# GPS.net
KiCad netlist of a schematic drawn in Altium Designer
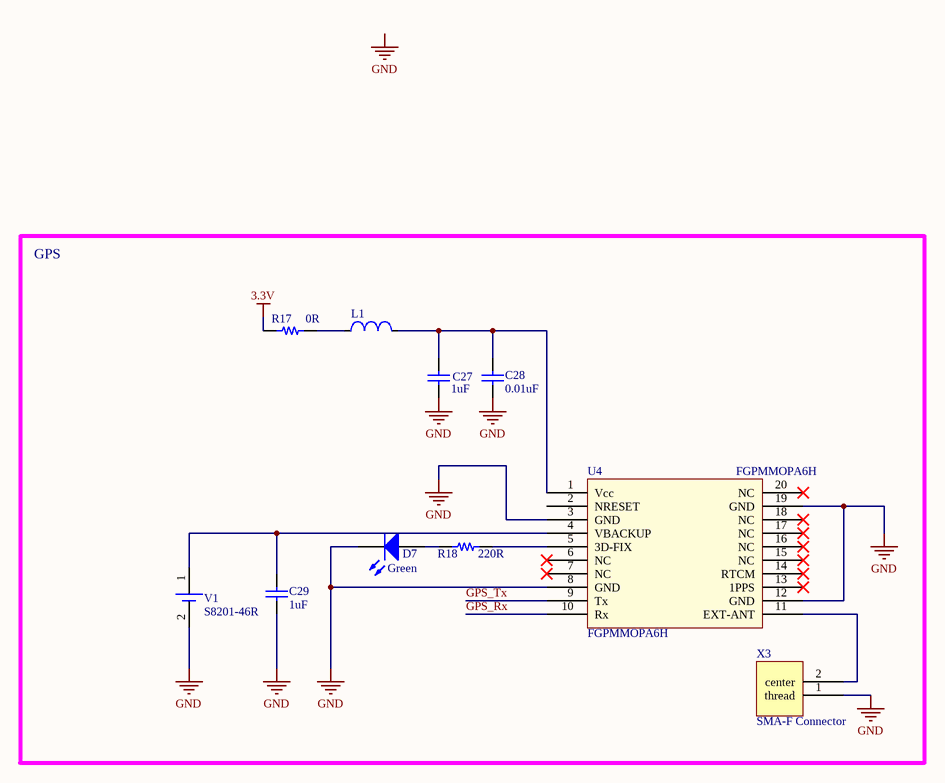
[diagram p0: GPS.SchDoc]

(export (version "E")
  (design (tool "Eeschema 10.0.6"))
  (components
    (comp (ref "C27")
      (value "1uF")
      (footprint "Capacitors:C0603")
      (description "1uF ceramic capacitor")
      (fields (field (name "MANUFACTURER") "TDK Corporation") (field (name "TOLERANCE") "20%"))
      (libsource (lib "Capacitors") (part "CAP CER 0603 1uF 25V X7R 20%"))
    )
    (comp (ref "C28")
      (value "0.01uF")
      (footprint "Capacitors:C0603")
      (description "0.01uF ceramic capacitor")
      (fields (field (name "MANUFACTURER") "TDK Corporation") (field (name "TOLERANCE") "10%"))
      (libsource (lib "Capacitors") (part "CAP CER 0603 0.01uF 50V X7R 10%"))
    )
    (comp (ref "C29")
      (value "1uF")
      (footprint "Capacitors:C0603")
      (description "1uF ceramic capacitor")
      (fields (field (name "MANUFACTURER") "Samsung Electro-Mechanics") (field (name "TOLERANCE") "10%"))
      (libsource (lib "Capacitors") (part "CAP CER 0603 1uF 16V X7R 10%"))
    )
    (comp (ref "D7")
      (value "Green")
      (footprint "LED1206")
      (description "Green LED 1206")
      (fields (field (name "MANUFACTURER") "Liteon") (field (name "PART_NUMBER") "LTST-C150KGKT"))
      (libsource (lib "Diodes") (part "LTST-C150KGKT"))
    )
    (comp (ref "L1")
      (value "Ferrite bead 60R@100MHz")
      (footprint "I0805")
      (description "0805 Ferrite bead, 60 Ohms at 100 MHz")
      (fields (field (name "MANUFACTURER") "Taiyo Yuden") (field (name "PART_NUMBER") "BKP2125HS600-T"))
      (libsource (lib "Inductors") (part "BKP2125HS600-T"))
    )
    (comp (ref "R17")
      (value "0R")
      (footprint "R0603")
      (description "0 Ohm Resistor")
      (fields (field (name "PART_NUMBER") "CRCW06030000Z0EA") (field (name "MANUFACTURER") "Vishay Dale"))
      (libsource (lib "Resistors") (part "RES 0603 0R"))
    )
    (comp (ref "R18")
      (value "220R")
      (footprint "Resistors:R0603")
      (description "220 Ohms resistor, 1/4W")
      (fields (field (name "MANUFACTURER") "Rohm Semiconductor") (field (name "PART_NUMBER") "ESR03EZPJ221"))
      (libsource (lib "Resistors") (part "RES 0603 220R 5% 1/4W"))
    )
    (comp (ref "U4")
      (value "FGPMMOPA6H")
      (footprint "FGPMMOPA6H")
      (description "GPS Standalone Module")
      (fields
        (field (name "MANUFACTURER") "GlobalTop Technology Inc.")
        (field (name "PART_NUMBER") "FGPMMOPA6H")
      )
      (libsource (lib "IC") (part "FGPMMOPA6H"))
    )
    (comp (ref "V1")
      (value "S8201-46R")
      (footprint "S8201-46R")
      (fields (field (name "MANUFACTURER") "Harwin Inc."))
      (libsource (lib "Other") (part "S8201-46R"))
    )
    (comp (ref "X3")
      (value "SMA-F Connector")
      (footprint "SMA-F")
      (description "SMA Connector Jack, Female Socket 50 Ohm Through Hole Solder")
      (fields
        (field (name "PART_NUMBER") "5-1814832-1")
        (field (name "MANUFACTURER") "TE Connectivity AMP Connectors")
      )
      (libsource (lib "Connectors") (part "5-1814832-1"))
    )
  )
  (nets
    (net (code "1") (name "/GPS_Rx") (class "Default")
      (node (ref "U4") (pin "10") (pinfunction "Rx_10") (pintype "passive"))
    )
    (net (code "2") (name "/GPS_Tx") (class "Default")
      (node (ref "U4") (pin "9") (pinfunction "Tx_9") (pintype "passive"))
    )
    (net (code "3") (name "3.3V") (class "Default")
      (node (ref "R17") (pin "1") (pinfunction "1_1") (pintype "passive"))
    )
    (net (code "4") (name "GND") (class "Default")
      (node (ref "C27") (pin "1") (pinfunction "1_1") (pintype "passive"))
      (node (ref "C28") (pin "1") (pinfunction "1_1") (pintype "passive"))
      (node (ref "C29") (pin "1") (pinfunction "1_1") (pintype "passive"))
      (node (ref "D7") (pin "2") (pinfunction "K_2") (pintype "passive"))
      (node (ref "U4") (pin "12") (pinfunction "GND_12") (pintype "passive"))
      (node (ref "U4") (pin "19") (pinfunction "GND_19") (pintype "passive"))
      (node (ref "U4") (pin "3") (pinfunction "GND_3") (pintype "passive"))
      (node (ref "U4") (pin "8") (pinfunction "GND_8") (pintype "passive"))
      (node (ref "V1") (pin "2") (pinfunction "2_2") (pintype "passive"))
      (node (ref "X3") (pin "1") (pinfunction "thread_1") (pintype "passive"))
    )
    (net (code "5") (name "Net-(D7-A)") (class "Default")
      (node (ref "D7") (pin "1") (pinfunction "A_1") (pintype "passive"))
      (node (ref "R18") (pin "1") (pinfunction "1_1") (pintype "passive"))
    )
    (net (code "6") (name "Net-(L1-Pad1)") (class "Default")
      (node (ref "L1") (pin "1") (pinfunction "1_1") (pintype "passive"))
      (node (ref "R17") (pin "2") (pinfunction "2_2") (pintype "passive"))
    )
    (net (code "7") (name "Net-(U4-3D-FIX)") (class "Default")
      (node (ref "R18") (pin "2") (pinfunction "2_2") (pintype "passive"))
      (node (ref "U4") (pin "5") (pinfunction "3D-FIX_5") (pintype "passive"))
    )
    (net (code "8") (name "Net-(U4-EXT-ANT)") (class "Default")
      (node (ref "U4") (pin "11") (pinfunction "EXT-ANT_11") (pintype "passive"))
      (node (ref "X3") (pin "2") (pinfunction "center_2") (pintype "passive"))
    )
    (net (code "9") (name "Net-(U4-VBACKUP)") (class "Default")
      (node (ref "C29") (pin "2") (pinfunction "2_2") (pintype "passive"))
      (node (ref "U4") (pin "4") (pinfunction "VBACKUP_4") (pintype "passive"))
      (node (ref "V1") (pin "1") (pinfunction "1_1") (pintype "passive"))
    )
    (net (code "10") (name "Net-(U4-Vcc)") (class "Default")
      (node (ref "C27") (pin "2") (pinfunction "2_2") (pintype "passive"))
      (node (ref "C28") (pin "2") (pinfunction "2_2") (pintype "passive"))
      (node (ref "L1") (pin "2") (pinfunction "2_2") (pintype "passive"))
      (node (ref "U4") (pin "1") (pinfunction "Vcc_1") (pintype "passive"))
    )
    (net (code "11") (name "unconnected-(U4-1PPS-Pad13)") (class "Default")
      (node (ref "U4") (pin "13") (pinfunction "1PPS_13") (pintype "passive+no_connect"))
    )
    (net (code "12") (name "unconnected-(U4-NC-Pad6)") (class "Default")
      (node (ref "U4") (pin "6") (pinfunction "NC_6") (pintype "passive+no_connect"))
    )
    (net (code "13") (name "unconnected-(U4-NC-Pad7)") (class "Default")
      (node (ref "U4") (pin "7") (pinfunction "NC_7") (pintype "passive+no_connect"))
    )
    (net (code "14") (name "unconnected-(U4-NC-Pad15)") (class "Default")
      (node (ref "U4") (pin "15") (pinfunction "NC_15") (pintype "passive+no_connect"))
    )
    (net (code "15") (name "unconnected-(U4-NC-Pad16)") (class "Default")
      (node (ref "U4") (pin "16") (pinfunction "NC_16") (pintype "passive+no_connect"))
    )
    (net (code "16") (name "unconnected-(U4-NC-Pad17)") (class "Default")
      (node (ref "U4") (pin "17") (pinfunction "NC_17") (pintype "passive+no_connect"))
    )
    (net (code "17") (name "unconnected-(U4-NC-Pad18)") (class "Default")
      (node (ref "U4") (pin "18") (pinfunction "NC_18") (pintype "passive+no_connect"))
    )
    (net (code "18") (name "unconnected-(U4-NC-Pad20)") (class "Default")
      (node (ref "U4") (pin "20") (pinfunction "NC_20") (pintype "passive+no_connect"))
    )
    (net (code "19") (name "unconnected-(U4-NRESET-Pad2)") (class "Default")
      (node (ref "U4") (pin "2") (pinfunction "NRESET_2") (pintype "passive"))
    )
    (net (code "20") (name "unconnected-(U4-RTCM-Pad14)") (class "Default")
      (node (ref "U4") (pin "14") (pinfunction "RTCM_14") (pintype "passive+no_connect"))
    )
  )
)
